# MCU.net
KiCad netlist of a schematic drawn in Altium Designer
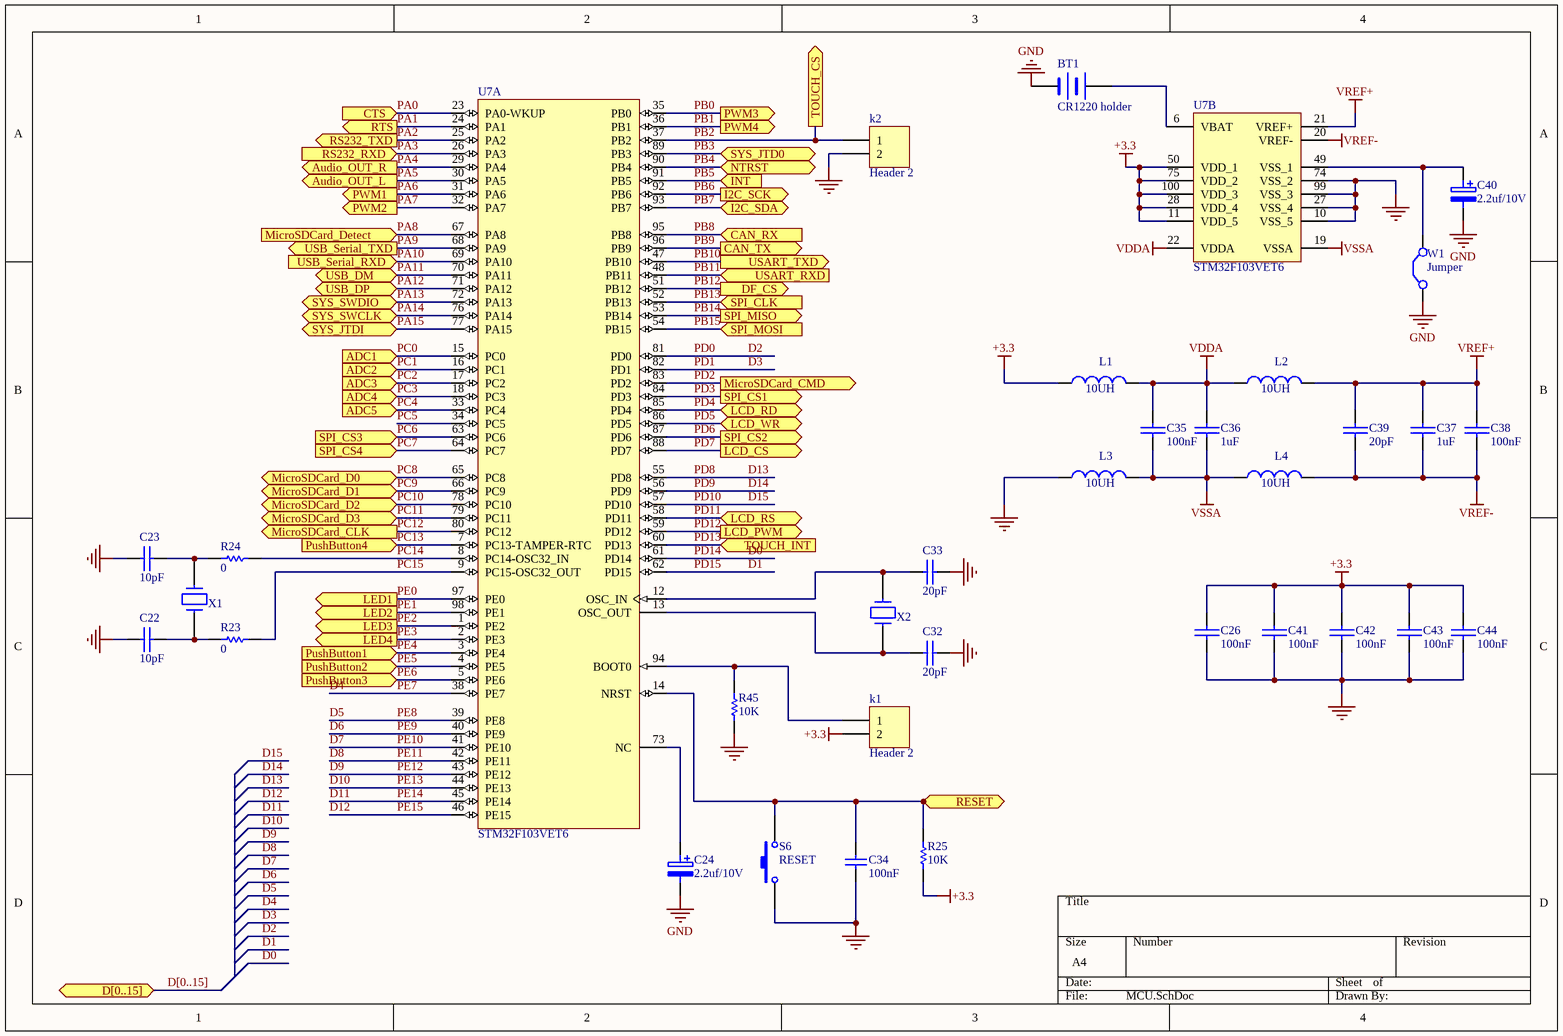
[diagram p0: MCU.SchDoc]

(export (version "E")
  (design (tool "Eeschema 10.0.6"))
  (components
    (comp (ref "BT1")
      (value "CR1220 holder")
      (footprint "BAT")
      (description "Battery")
      (libsource (lib "*") (part "BATTERY"))
    )
    (comp (ref "C22")
      (value "10pF")
      (footprint "1206")
      (description "Capacitor")
      (libsource (lib "") (part "CAP_1"))
    )
    (comp (ref "C23")
      (value "10pF")
      (footprint "1206")
      (description "Capacitor")
      (libsource (lib "") (part "CAP_1"))
    )
    (comp (ref "C24")
      (value "2.2uf/10V")
      (footprint "1210")
      (description "Electrolytic Capacitor")
      (libsource (lib "*") (part "ELECTRO2"))
    )
    (comp (ref "C26")
      (value "100nF")
      (footprint "0805")
      (description "Capacitor")
      (libsource (lib "*") (part "CAP"))
    )
    (comp (ref "C32")
      (value "20pF")
      (footprint "1206")
      (description "Capacitor")
      (libsource (lib "*") (part "CAP"))
    )
    (comp (ref "C33")
      (value "20pF")
      (footprint "1206")
      (description "Capacitor")
      (libsource (lib "*") (part "CAP"))
    )
    (comp (ref "C34")
      (value "100nF")
      (footprint "1206")
      (description "Capacitor")
      (fields (field (name "PUBLISHER") "Altium Limited"))
      (libsource (lib "Miscellaneous Devices") (part "CAP"))
    )
    (comp (ref "C35")
      (value "100nF")
      (footprint "1206")
      (description "Capacitor")
      (libsource (lib "*") (part "CAP"))
    )
    (comp (ref "C36")
      (value "1uF")
      (footprint "1206")
      (description "Capacitor")
      (libsource (lib "*") (part "CAP"))
    )
    (comp (ref "C37")
      (value "1uF")
      (footprint "1206")
      (description "Capacitor")
      (libsource (lib "*") (part "CAP"))
    )
    (comp (ref "C38")
      (value "100nF")
      (footprint "1206")
      (description "Capacitor")
      (libsource (lib "*") (part "CAP"))
    )
    (comp (ref "C39")
      (value "20pF")
      (footprint "1206")
      (description "Capacitor")
      (libsource (lib "*") (part "CAP"))
    )
    (comp (ref "C40")
      (value "2.2uf/10V")
      (footprint "1210")
      (description "Electrolytic Capacitor")
      (libsource (lib "*") (part "ELECTRO2"))
    )
    (comp (ref "C41")
      (value "100nF")
      (footprint "0805")
      (description "Capacitor")
      (libsource (lib "*") (part "CAP"))
    )
    (comp (ref "C42")
      (value "100nF")
      (footprint "0805")
      (description "Capacitor")
      (libsource (lib "*") (part "CAP"))
    )
    (comp (ref "C43")
      (value "100nF")
      (footprint "0805")
      (description "Capacitor")
      (libsource (lib "*") (part "CAP"))
    )
    (comp (ref "C44")
      (value "100nF")
      (footprint "0805")
      (description "Capacitor")
      (libsource (lib "*") (part "CAP"))
    )
    (comp (ref "k1")
      (value "Header 2")
      (footprint "SIP2")
      (description "Header, 2-Pin")
      (fields (field (name "PUBLISHER") "Altium Limited"))
      (libsource (lib "Miscellaneous Connectors") (part "Header 2"))
    )
    (comp (ref "k2")
      (value "Header 2")
      (footprint "SIP2")
      (description "Header, 2-Pin")
      (fields (field (name "PUBLISHER") "Altium Limited"))
      (libsource (lib "Miscellaneous Connectors") (part "Header 2"))
    )
    (comp (ref "L1")
      (value "10UH")
      (footprint "L1206")
      (description "Inductor")
      (fields (field (name "PUBLISHER") "Altium Limited"))
      (libsource (lib "Miscellaneous Devices") (part "Inductor"))
    )
    (comp (ref "L2")
      (value "10UH")
      (footprint "L1206")
      (description "Inductor")
      (fields (field (name "PUBLISHER") "Altium Limited"))
      (libsource (lib "Miscellaneous Devices") (part "Inductor"))
    )
    (comp (ref "L3")
      (value "10UH")
      (footprint "L1206")
      (description "Inductor")
      (fields (field (name "PUBLISHER") "Altium Limited"))
      (libsource (lib "Miscellaneous Devices") (part "Inductor"))
    )
    (comp (ref "L4")
      (value "10UH")
      (footprint "L1206")
      (description "Inductor")
      (fields (field (name "PUBLISHER") "Altium Limited"))
      (libsource (lib "Miscellaneous Devices") (part "Inductor"))
    )
    (comp (ref "R23")
      (value "0")
      (footprint "R1206")
      (description "Resistor")
      (fields (field (name "PUBLISHER") "Altium Limited"))
      (libsource (lib "Miscellaneous Devices") (part "Res1"))
    )
    (comp (ref "R24")
      (value "0")
      (footprint "R1206")
      (description "Resistor")
      (fields (field (name "PUBLISHER") "Altium Limited"))
      (libsource (lib "Miscellaneous Devices") (part "Res1"))
    )
    (comp (ref "R25")
      (value "10K")
      (footprint "R1206")
      (description "Resistor")
      (fields (field (name "PUBLISHER") "Altium Limited"))
      (libsource (lib "Miscellaneous Devices") (part "res1"))
    )
    (comp (ref "R45")
      (value "10K")
      (description "Resistor")
      (fields (field (name "PUBLISHER") "Altium Limited"))
      (libsource (lib "Miscellaneous Devices") (part "res1"))
    )
    (comp (ref "S6")
      (value "RESET")
      (footprint "SWSMD")
      (description "Switch")
      (fields (field (name "PUBLISHER") "Altium Limited"))
      (libsource (lib "Miscellaneous Devices") (part "SW-PB"))
    )
    (comp (ref "U7")
      (value "STM32F103VET6")
      (footprint "STM-LQFP100_N")
      (libsource (lib "STMicroelectronics STM32 F1") (part "STM32F103VET6"))
    )
    (comp (ref "W1")
      (value "Jumper")
      (footprint "JP2_SMD")
      (description "Jumper Wire")
      (fields (field (name "PUBLISHER") "Altium Limited"))
      (libsource (lib "Miscellaneous Devices") (part "Jumper"))
    )
    (comp (ref "X1")
      (value "HC-49S-C16QSA-8M(jfvny)(with socket)")
      (footprint "Xtal1")
      (description "Crystal")
      (libsource (lib "*") (part "CRYSTAL"))
    )
    (comp (ref "X2")
      (value "HC-49S-C16QSA-8M(jfvny)(with socket)")
      (footprint "XTAL3")
      (description "Crystal")
      (libsource (lib "*") (part "CRYSTAL"))
    )
  )
  (nets
    (net (code "1") (name "+3.3") (class "Default")
      (node (ref "C26") (pin "2") (pinfunction "2_2") (pintype "passive"))
      (node (ref "C41") (pin "2") (pinfunction "2_2") (pintype "passive"))
      (node (ref "C42") (pin "2") (pinfunction "2_2") (pintype "passive"))
      (node (ref "C43") (pin "2") (pinfunction "2_2") (pintype "passive"))
      (node (ref "C44") (pin "2") (pinfunction "2_2") (pintype "passive"))
      (node (ref "L1") (pin "1") (pinfunction "1_1") (pintype "passive"))
      (node (ref "R25") (pin "1") (pinfunction "1_1") (pintype "passive"))
      (node (ref "U7") (pin "100") (pinfunction "VDD_3_100") (pintype "power_in"))
      (node (ref "U7") (pin "11") (pinfunction "VDD_5_11") (pintype "power_in"))
      (node (ref "U7") (pin "28") (pinfunction "VDD_4_28") (pintype "power_in"))
      (node (ref "U7") (pin "50") (pinfunction "VDD_1_50") (pintype "power_in"))
      (node (ref "U7") (pin "75") (pinfunction "VDD_2_75") (pintype "power_in"))
      (node (ref "k1") (pin "2") (pinfunction "2_2") (pintype "passive"))
    )
    (net (code "2") (name "/D0") (class "Default")
      (node (ref "U7") (pin "61") (pinfunction "PD14_61") (pintype "bidirectional"))
    )
    (net (code "3") (name "/D1") (class "Default")
      (node (ref "U7") (pin "62") (pinfunction "PD15_62") (pintype "bidirectional"))
    )
    (net (code "4") (name "/D2") (class "Default")
      (node (ref "U7") (pin "81") (pinfunction "PD0_81") (pintype "bidirectional"))
    )
    (net (code "5") (name "/D3") (class "Default")
      (node (ref "U7") (pin "82") (pinfunction "PD1_82") (pintype "bidirectional"))
    )
    (net (code "6") (name "/D4") (class "Default")
      (node (ref "U7") (pin "38") (pinfunction "PE7_38") (pintype "bidirectional"))
    )
    (net (code "7") (name "/D5") (class "Default")
      (node (ref "U7") (pin "39") (pinfunction "PE8_39") (pintype "bidirectional"))
    )
    (net (code "8") (name "/D6") (class "Default")
      (node (ref "U7") (pin "40") (pinfunction "PE9_40") (pintype "bidirectional"))
    )
    (net (code "9") (name "/D7") (class "Default")
      (node (ref "U7") (pin "41") (pinfunction "PE10_41") (pintype "bidirectional"))
    )
    (net (code "10") (name "/D8") (class "Default")
      (node (ref "U7") (pin "42") (pinfunction "PE11_42") (pintype "bidirectional"))
    )
    (net (code "11") (name "/D9") (class "Default")
      (node (ref "U7") (pin "43") (pinfunction "PE12_43") (pintype "bidirectional"))
    )
    (net (code "12") (name "/D10") (class "Default")
      (node (ref "U7") (pin "44") (pinfunction "PE13_44") (pintype "bidirectional"))
    )
    (net (code "13") (name "/D11") (class "Default")
      (node (ref "U7") (pin "45") (pinfunction "PE14_45") (pintype "bidirectional"))
    )
    (net (code "14") (name "/D12") (class "Default")
      (node (ref "U7") (pin "46") (pinfunction "PE15_46") (pintype "bidirectional"))
    )
    (net (code "15") (name "/D13") (class "Default")
      (node (ref "U7") (pin "55") (pinfunction "PD8_55") (pintype "bidirectional"))
    )
    (net (code "16") (name "/D14") (class "Default")
      (node (ref "U7") (pin "56") (pinfunction "PD9_56") (pintype "bidirectional"))
    )
    (net (code "17") (name "/D15") (class "Default")
      (node (ref "U7") (pin "57") (pinfunction "PD10_57") (pintype "bidirectional"))
    )
    (net (code "19") (name "/PA0") (class "Default")
      (node (ref "U7") (pin "23") (pinfunction "PA0-WKUP_23") (pintype "bidirectional"))
    )
    (net (code "20") (name "/PA1") (class "Default")
      (node (ref "U7") (pin "24") (pinfunction "PA1_24") (pintype "bidirectional"))
    )
    (net (code "21") (name "/PA2") (class "Default")
      (node (ref "U7") (pin "25") (pinfunction "PA2_25") (pintype "bidirectional"))
    )
    (net (code "22") (name "/PA3") (class "Default")
      (node (ref "U7") (pin "26") (pinfunction "PA3_26") (pintype "bidirectional"))
    )
    (net (code "23") (name "/PA4") (class "Default")
      (node (ref "U7") (pin "29") (pinfunction "PA4_29") (pintype "bidirectional"))
    )
    (net (code "24") (name "/PA5") (class "Default")
      (node (ref "U7") (pin "30") (pinfunction "PA5_30") (pintype "bidirectional"))
    )
    (net (code "25") (name "/PA6") (class "Default")
      (node (ref "U7") (pin "31") (pinfunction "PA6_31") (pintype "bidirectional"))
    )
    (net (code "26") (name "/PA7") (class "Default")
      (node (ref "U7") (pin "32") (pinfunction "PA7_32") (pintype "bidirectional"))
    )
    (net (code "27") (name "/PA8") (class "Default")
      (node (ref "U7") (pin "67") (pinfunction "PA8_67") (pintype "bidirectional"))
    )
    (net (code "28") (name "/PA9") (class "Default")
      (node (ref "U7") (pin "68") (pinfunction "PA9_68") (pintype "bidirectional"))
    )
    (net (code "29") (name "/PA10") (class "Default")
      (node (ref "U7") (pin "69") (pinfunction "PA10_69") (pintype "bidirectional"))
    )
    (net (code "30") (name "/PA11") (class "Default")
      (node (ref "U7") (pin "70") (pinfunction "PA11_70") (pintype "bidirectional"))
    )
    (net (code "31") (name "/PA12") (class "Default")
      (node (ref "U7") (pin "71") (pinfunction "PA12_71") (pintype "bidirectional"))
    )
    (net (code "32") (name "/PA13") (class "Default")
      (node (ref "U7") (pin "72") (pinfunction "PA13_72") (pintype "bidirectional"))
    )
    (net (code "33") (name "/PA14") (class "Default")
      (node (ref "U7") (pin "76") (pinfunction "PA14_76") (pintype "bidirectional"))
    )
    (net (code "34") (name "/PA15") (class "Default")
      (node (ref "U7") (pin "77") (pinfunction "PA15_77") (pintype "bidirectional"))
    )
    (net (code "35") (name "/PB0") (class "Default")
      (node (ref "U7") (pin "35") (pinfunction "PB0_35") (pintype "bidirectional"))
    )
    (net (code "36") (name "/PB1") (class "Default")
      (node (ref "U7") (pin "36") (pinfunction "PB1_36") (pintype "bidirectional"))
    )
    (net (code "37") (name "/PB2") (class "Default")
      (node (ref "U7") (pin "37") (pinfunction "PB2_37") (pintype "bidirectional"))
      (node (ref "k2") (pin "1") (pinfunction "1_1") (pintype "passive"))
    )
    (net (code "38") (name "/PB3") (class "Default")
      (node (ref "U7") (pin "89") (pinfunction "PB3_89") (pintype "bidirectional"))
    )
    (net (code "39") (name "/PB4") (class "Default")
      (node (ref "U7") (pin "90") (pinfunction "PB4_90") (pintype "bidirectional"))
    )
    (net (code "40") (name "/PB5") (class "Default")
      (node (ref "U7") (pin "91") (pinfunction "PB5_91") (pintype "bidirectional"))
    )
    (net (code "41") (name "/PB6") (class "Default")
      (node (ref "U7") (pin "92") (pinfunction "PB6_92") (pintype "bidirectional"))
    )
    (net (code "42") (name "/PB7") (class "Default")
      (node (ref "U7") (pin "93") (pinfunction "PB7_93") (pintype "bidirectional"))
    )
    (net (code "43") (name "/PB8") (class "Default")
      (node (ref "U7") (pin "95") (pinfunction "PB8_95") (pintype "bidirectional"))
    )
    (net (code "44") (name "/PB9") (class "Default")
      (node (ref "U7") (pin "96") (pinfunction "PB9_96") (pintype "bidirectional"))
    )
    (net (code "45") (name "/PB10") (class "Default")
      (node (ref "U7") (pin "47") (pinfunction "PB10_47") (pintype "bidirectional"))
    )
    (net (code "46") (name "/PB11") (class "Default")
      (node (ref "U7") (pin "48") (pinfunction "PB11_48") (pintype "bidirectional"))
    )
    (net (code "47") (name "/PB12") (class "Default")
      (node (ref "U7") (pin "51") (pinfunction "PB12_51") (pintype "bidirectional"))
    )
    (net (code "48") (name "/PB13") (class "Default")
      (node (ref "U7") (pin "52") (pinfunction "PB13_52") (pintype "bidirectional"))
    )
    (net (code "49") (name "/PB14") (class "Default")
      (node (ref "U7") (pin "53") (pinfunction "PB14_53") (pintype "bidirectional"))
    )
    (net (code "50") (name "/PB15") (class "Default")
      (node (ref "U7") (pin "54") (pinfunction "PB15_54") (pintype "bidirectional"))
    )
    (net (code "51") (name "/PC0") (class "Default")
      (node (ref "U7") (pin "15") (pinfunction "PC0_15") (pintype "bidirectional"))
    )
    (net (code "52") (name "/PC1") (class "Default")
      (node (ref "U7") (pin "16") (pinfunction "PC1_16") (pintype "bidirectional"))
    )
    (net (code "53") (name "/PC2") (class "Default")
      (node (ref "U7") (pin "17") (pinfunction "PC2_17") (pintype "bidirectional"))
    )
    (net (code "54") (name "/PC3") (class "Default")
      (node (ref "U7") (pin "18") (pinfunction "PC3_18") (pintype "bidirectional"))
    )
    (net (code "55") (name "/PC4") (class "Default")
      (node (ref "U7") (pin "33") (pinfunction "PC4_33") (pintype "bidirectional"))
    )
    (net (code "56") (name "/PC5") (class "Default")
      (node (ref "U7") (pin "34") (pinfunction "PC5_34") (pintype "bidirectional"))
    )
    (net (code "57") (name "/PC6") (class "Default")
      (node (ref "U7") (pin "63") (pinfunction "PC6_63") (pintype "bidirectional"))
    )
    (net (code "58") (name "/PC7") (class "Default")
      (node (ref "U7") (pin "64") (pinfunction "PC7_64") (pintype "bidirectional"))
    )
    (net (code "59") (name "/PC8") (class "Default")
      (node (ref "U7") (pin "65") (pinfunction "PC8_65") (pintype "bidirectional"))
    )
    (net (code "60") (name "/PC9") (class "Default")
      (node (ref "U7") (pin "66") (pinfunction "PC9_66") (pintype "bidirectional"))
    )
    (net (code "61") (name "/PC10") (class "Default")
      (node (ref "U7") (pin "78") (pinfunction "PC10_78") (pintype "bidirectional"))
    )
    (net (code "62") (name "/PC11") (class "Default")
      (node (ref "U7") (pin "79") (pinfunction "PC11_79") (pintype "bidirectional"))
    )
    (net (code "63") (name "/PC12") (class "Default")
      (node (ref "U7") (pin "80") (pinfunction "PC12_80") (pintype "bidirectional"))
    )
    (net (code "64") (name "/PC13") (class "Default")
      (node (ref "U7") (pin "7") (pinfunction "PC13-TAMPER-RTC_7") (pintype "bidirectional"))
    )
    (net (code "65") (name "/PC14") (class "Default")
      (node (ref "R24") (pin "2") (pinfunction "2_2") (pintype "passive"))
      (node (ref "U7") (pin "8") (pinfunction "PC14-OSC32_IN_8") (pintype "bidirectional"))
    )
    (net (code "66") (name "/PC15") (class "Default")
      (node (ref "R23") (pin "2") (pinfunction "2_2") (pintype "passive"))
      (node (ref "U7") (pin "9") (pinfunction "PC15-OSC32_OUT_9") (pintype "bidirectional"))
    )
    (net (code "67") (name "/PD2") (class "Default")
      (node (ref "U7") (pin "83") (pinfunction "PD2_83") (pintype "bidirectional"))
    )
    (net (code "68") (name "/PD3") (class "Default")
      (node (ref "U7") (pin "84") (pinfunction "PD3_84") (pintype "bidirectional"))
    )
    (net (code "69") (name "/PD4") (class "Default")
      (node (ref "U7") (pin "85") (pinfunction "PD4_85") (pintype "bidirectional"))
    )
    (net (code "70") (name "/PD5") (class "Default")
      (node (ref "U7") (pin "86") (pinfunction "PD5_86") (pintype "bidirectional"))
    )
    (net (code "71") (name "/PD6") (class "Default")
      (node (ref "U7") (pin "87") (pinfunction "PD6_87") (pintype "bidirectional"))
    )
    (net (code "72") (name "/PD7") (class "Default")
      (node (ref "U7") (pin "88") (pinfunction "PD7_88") (pintype "bidirectional"))
    )
    (net (code "73") (name "/PD11") (class "Default")
      (node (ref "U7") (pin "58") (pinfunction "PD11_58") (pintype "bidirectional"))
    )
    (net (code "74") (name "/PD12") (class "Default")
      (node (ref "U7") (pin "59") (pinfunction "PD12_59") (pintype "bidirectional"))
    )
    (net (code "75") (name "/PD13") (class "Default")
      (node (ref "U7") (pin "60") (pinfunction "PD13_60") (pintype "bidirectional"))
    )
    (net (code "76") (name "/PE0") (class "Default")
      (node (ref "U7") (pin "97") (pinfunction "PE0_97") (pintype "bidirectional"))
    )
    (net (code "77") (name "/PE1") (class "Default")
      (node (ref "U7") (pin "98") (pinfunction "PE1_98") (pintype "bidirectional"))
    )
    (net (code "78") (name "/PE2") (class "Default")
      (node (ref "U7") (pin "1") (pinfunction "PE2_1") (pintype "bidirectional"))
    )
    (net (code "79") (name "/PE3") (class "Default")
      (node (ref "U7") (pin "2") (pinfunction "PE3_2") (pintype "bidirectional"))
    )
    (net (code "80") (name "/PE4") (class "Default")
      (node (ref "U7") (pin "3") (pinfunction "PE4_3") (pintype "bidirectional"))
    )
    (net (code "81") (name "/PE5") (class "Default")
      (node (ref "U7") (pin "4") (pinfunction "PE5_4") (pintype "bidirectional"))
    )
    (net (code "82") (name "/PE6") (class "Default")
      (node (ref "U7") (pin "5") (pinfunction "PE6_5") (pintype "bidirectional"))
    )
    (net (code "83") (name "/RESET") (class "Default")
      (node (ref "C34") (pin "2") (pinfunction "2_2") (pintype "passive"))
      (node (ref "R25") (pin "2") (pinfunction "2_2") (pintype "passive"))
      (node (ref "S6") (pin "2") (pinfunction "2_2") (pintype "passive"))
      (node (ref "U7") (pin "14") (pinfunction "NRST_14") (pintype "bidirectional"))
    )
    (net (code "84") (name "GND") (class "Default")
      (node (ref "BT1") (pin "2") (pinfunction "-_2") (pintype "passive"))
      (node (ref "C22") (pin "2") (pinfunction "2_2") (pintype "passive"))
      (node (ref "C23") (pin "2") (pinfunction "2_2") (pintype "passive"))
      (node (ref "C24") (pin "2") (pinfunction "2_2") (pintype "passive"))
      (node (ref "C26") (pin "1") (pinfunction "1_1") (pintype "passive"))
      (node (ref "C32") (pin "2") (pinfunction "2_2") (pintype "passive"))
      (node (ref "C33") (pin "2") (pinfunction "2_2") (pintype "passive"))
      (node (ref "C34") (pin "1") (pinfunction "1_1") (pintype "passive"))
      (node (ref "C40") (pin "2") (pinfunction "2_2") (pintype "passive"))
      (node (ref "C41") (pin "1") (pinfunction "1_1") (pintype "passive"))
      (node (ref "C42") (pin "1") (pinfunction "1_1") (pintype "passive"))
      (node (ref "C43") (pin "1") (pinfunction "1_1") (pintype "passive"))
      (node (ref "C44") (pin "1") (pinfunction "1_1") (pintype "passive"))
      (node (ref "L3") (pin "1") (pinfunction "1_1") (pintype "passive"))
      (node (ref "R45") (pin "1") (pinfunction "1_1") (pintype "passive"))
      (node (ref "S6") (pin "1") (pinfunction "1_1") (pintype "passive"))
      (node (ref "U7") (pin "10") (pinfunction "VSS_5_10") (pintype "power_in"))
      (node (ref "U7") (pin "27") (pinfunction "VSS_4_27") (pintype "power_in"))
      (node (ref "U7") (pin "74") (pinfunction "VSS_2_74") (pintype "power_in"))
      (node (ref "U7") (pin "99") (pinfunction "VSS_3_99") (pintype "power_in"))
      (node (ref "W1") (pin "1") (pinfunction "C1_1") (pintype "passive"))
      (node (ref "k2") (pin "2") (pinfunction "2_2") (pintype "passive"))
    )
    (net (code "85") (name "Net-(BT1-+)") (class "Default")
      (node (ref "BT1") (pin "1") (pinfunction "+_1") (pintype "passive"))
      (node (ref "U7") (pin "6") (pinfunction "VBAT_6") (pintype "power_in"))
    )
    (net (code "86") (name "Net-(C22-Pad1)") (class "Default")
      (node (ref "C22") (pin "1") (pinfunction "1_1") (pintype "passive"))
      (node (ref "R23") (pin "1") (pinfunction "1_1") (pintype "passive"))
      (node (ref "X1") (pin "2") (pinfunction "2_2") (pintype "passive"))
    )
    (net (code "87") (name "Net-(C23-Pad1)") (class "Default")
      (node (ref "C23") (pin "1") (pinfunction "1_1") (pintype "passive"))
      (node (ref "R24") (pin "1") (pinfunction "1_1") (pintype "passive"))
      (node (ref "X1") (pin "1") (pinfunction "1_1") (pintype "passive"))
    )
    (net (code "88") (name "Net-(U7A-BOOT0)") (class "Default")
      (node (ref "R45") (pin "2") (pinfunction "2_2") (pintype "passive"))
      (node (ref "U7") (pin "94") (pinfunction "BOOT0_94") (pintype "input"))
      (node (ref "k1") (pin "1") (pinfunction "1_1") (pintype "passive"))
    )
    (net (code "89") (name "Net-(U7A-NC)") (class "Default")
      (node (ref "C24") (pin "1") (pinfunction "1_1") (pintype "passive"))
      (node (ref "U7") (pin "73") (pinfunction "NC_73") (pintype "passive"))
    )
    (net (code "90") (name "Net-(U7A-OSC_IN)") (class "Default")
      (node (ref "C33") (pin "1") (pinfunction "1_1") (pintype "passive"))
      (node (ref "U7") (pin "12") (pinfunction "OSC_IN_12") (pintype "input"))
      (node (ref "X2") (pin "1") (pinfunction "1_1") (pintype "passive"))
    )
    (net (code "91") (name "Net-(U7A-OSC_OUT)") (class "Default")
      (node (ref "C32") (pin "1") (pinfunction "1_1") (pintype "passive"))
      (node (ref "U7") (pin "13") (pinfunction "OSC_OUT_13") (pintype "passive"))
      (node (ref "X2") (pin "2") (pinfunction "2_2") (pintype "passive"))
    )
    (net (code "92") (name "Net-(U7B-VSS_1)") (class "Default")
      (node (ref "C40") (pin "1") (pinfunction "1_1") (pintype "passive"))
      (node (ref "U7") (pin "49") (pinfunction "VSS_1_49") (pintype "power_in"))
      (node (ref "W1") (pin "2") (pinfunction "C2_2") (pintype "passive"))
    )
    (net (code "93") (name "VDDA") (class "Default")
      (node (ref "C35") (pin "2") (pinfunction "2_2") (pintype "passive"))
      (node (ref "C36") (pin "2") (pinfunction "2_2") (pintype "passive"))
      (node (ref "L1") (pin "2") (pinfunction "2_2") (pintype "passive"))
      (node (ref "L2") (pin "1") (pinfunction "1_1") (pintype "passive"))
      (node (ref "U7") (pin "22") (pinfunction "VDDA_22") (pintype "power_in"))
    )
    (net (code "94") (name "VREF+") (class "Default")
      (node (ref "C37") (pin "2") (pinfunction "2_2") (pintype "passive"))
      (node (ref "C38") (pin "2") (pinfunction "2_2") (pintype "passive"))
      (node (ref "C39") (pin "2") (pinfunction "2_2") (pintype "passive"))
      (node (ref "L2") (pin "2") (pinfunction "2_2") (pintype "passive"))
      (node (ref "U7") (pin "21") (pinfunction "VREF+_21") (pintype "power_in"))
    )
    (net (code "95") (name "VREF-") (class "Default")
      (node (ref "C37") (pin "1") (pinfunction "1_1") (pintype "passive"))
      (node (ref "C38") (pin "1") (pinfunction "1_1") (pintype "passive"))
      (node (ref "C39") (pin "1") (pinfunction "1_1") (pintype "passive"))
      (node (ref "L4") (pin "2") (pinfunction "2_2") (pintype "passive"))
      (node (ref "U7") (pin "20") (pinfunction "VREF-_20") (pintype "power_in"))
    )
    (net (code "96") (name "VSSA") (class "Default")
      (node (ref "C35") (pin "1") (pinfunction "1_1") (pintype "passive"))
      (node (ref "C36") (pin "1") (pinfunction "1_1") (pintype "passive"))
      (node (ref "L3") (pin "2") (pinfunction "2_2") (pintype "passive"))
      (node (ref "L4") (pin "1") (pinfunction "1_1") (pintype "passive"))
      (node (ref "U7") (pin "19") (pinfunction "VSSA_19") (pintype "power_in"))
    )
  )
)
